# 02-GPRS.net
KiCad netlist of a schematic drawn in Altium Designer
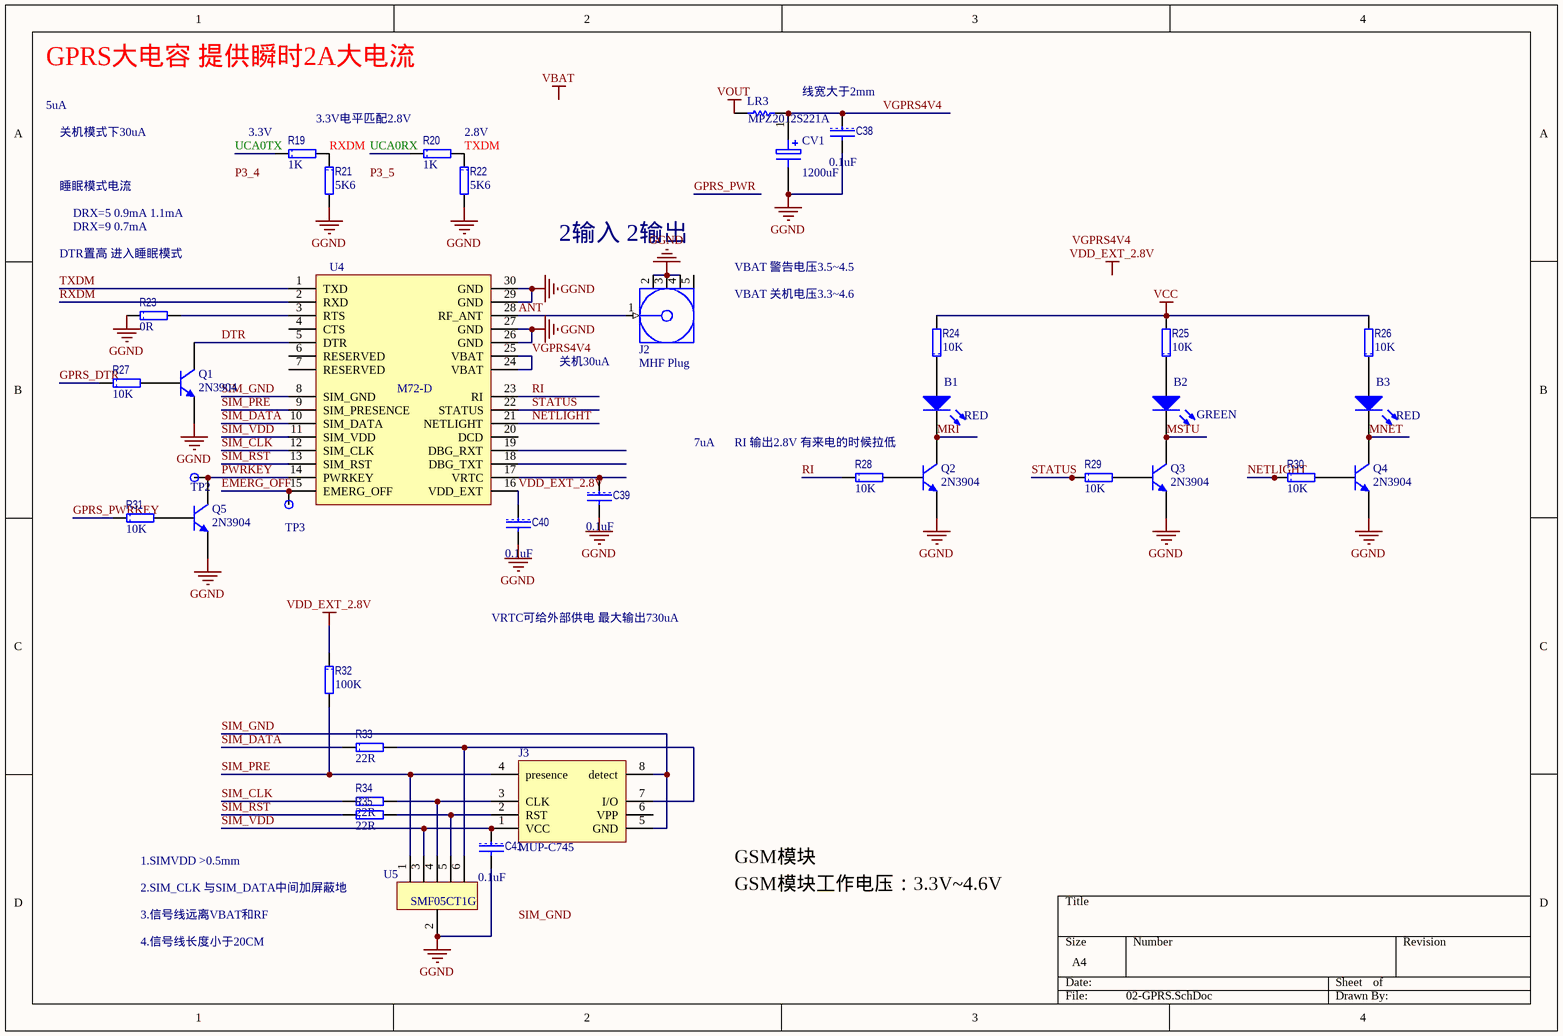
[diagram p0: 02-GPRS.SchDoc]

(export (version "E")
  (design (tool "Eeschema 10.0.6"))
  (components
    (comp (ref "B1")
      (value "RED")
      (footprint "0805LED")
      (description "Typical RED, GREEN, YELLOW, AMBER GaAs LED")
      (fields (field (name "PUBLISHER") "Altium Limited"))
      (libsource (lib "Miscellaneous Devices") (part "LED2"))
    )
    (comp (ref "B2")
      (value "GREEN")
      (footprint "0805LED")
      (description "Typical RED, GREEN, YELLOW, AMBER GaAs LED")
      (fields (field (name "PUBLISHER") "Altium Limited"))
      (libsource (lib "Miscellaneous Devices") (part "LED2"))
    )
    (comp (ref "B3")
      (value "RED")
      (footprint "0805LED")
      (description "Typical RED, GREEN, YELLOW, AMBER GaAs LED")
      (fields (field (name "PUBLISHER") "Altium Limited"))
      (libsource (lib "Miscellaneous Devices") (part "LED2"))
    )
    (comp (ref "C38")
      (value "0.1uF")
      (footprint "1608[0603]C")
      (description "多层陶瓷电容器MLCC - SMD/SMT 0603 0.1uF 50volts X7R 10%")
      (fields (field (name "MANUFACTURER") "TDK") (field (name "MANUFACTURER PART NUMBER") "C1608X7R1H104K"))
      (libsource (lib "*") (part "CAP"))
    )
    (comp (ref "C39")
      (value "0.1uF")
      (footprint "1608[0603]C")
      (description "多层陶瓷电容器MLCC - SMD/SMT 0603 0.1uF 50volts X7R 10%")
      (fields (field (name "MANUFACTURER") "TDK") (field (name "MANUFACTURER PART NUMBER") "C1608X7R1H104K"))
      (libsource (lib "*") (part "CAP"))
    )
    (comp (ref "C40")
      (value "0.1uF")
      (footprint "1608[0603]C")
      (description "多层陶瓷电容器MLCC - SMD/SMT 0603 0.1uF 50volts X7R 10%")
      (fields (field (name "MANUFACTURER") "TDK") (field (name "MANUFACTURER PART NUMBER") "C1608X7R1H104K"))
      (libsource (lib "*") (part "CAP"))
    )
    (comp (ref "C41")
      (value "0.1uF")
      (footprint "1608[0603]C")
      (description "多层陶瓷电容器MLCC - SMD/SMT 0603 0.1uF 50volts X7R 10%")
      (fields (field (name "MANUFACTURER") "TDK") (field (name "MANUFACTURER PART NUMBER") "C1608X7R1H104K"))
      (libsource (lib "*") (part "CAP"))
    )
    (comp (ref "CV1")
      (value "1200uF")
      (footprint "CAPPR5-10x20/H1.1")
      (description "插针 铝质电解电容器 - 带引线 1200uF 10V")
      (fields
        (field (name "MANUFACTURER") "Panasonic Electronic Components")
        (field (name "MANUFACTURER PART NUMBER") "EEU-FC1A122")
      )
      (libsource (lib "*") (part "ELECTRO1"))
    )
    (comp (ref "J2")
      (value "MHF Plug")
      (footprint "MHF[MCB3]-V4")
      (description "插针 RF 连接器 ONBRD IPEX MHF RECEPTACLE")
      (fields
        (field (name "MANUFACTURER") "Taoglas")
        (field (name "MANUFACTURER PART NUMBER") "RECE-20279-001E-01")
      )
      (libsource (lib "Miscellaneous Connectors") (part "COAX-F"))
    )
    (comp (ref "J3")
      (value "MUP-C745")
      (footprint "MUP-C745")
      (description "CON")
      (libsource (lib "*") (part "SIMCARD"))
    )
    (comp (ref "LR3")
      (value "MPZ2012S221A")
      (footprint "2012[0805]")
      (description "电磁干扰滤波珠子、扼流圈和阵列 Ferrite Chip Beads")
      (fields (field (name "MANUFACTURER") "TDK"))
      (libsource (lib "Miscellaneous Devices") (part "Res Semi"))
    )
    (comp (ref "Q1")
      (value "2N3904")
      (footprint "SOT23_N")
      (description "NPN General Purpose Amplifier")
      (fields (field (name "PUBLISHER") "Altium Limited"))
      (libsource (lib "Miscellaneous Devices") (part "2N3904"))
    )
    (comp (ref "Q2")
      (value "2N3904")
      (footprint "SOT23_N")
      (description "NPN General Purpose Amplifier")
      (fields (field (name "PUBLISHER") "Altium Limited"))
      (libsource (lib "Miscellaneous Devices") (part "2N3904"))
    )
    (comp (ref "Q3")
      (value "2N3904")
      (footprint "SOT23_N")
      (description "NPN General Purpose Amplifier")
      (fields (field (name "PUBLISHER") "Altium Limited"))
      (libsource (lib "Miscellaneous Devices") (part "2N3904"))
    )
    (comp (ref "Q4")
      (value "2N3904")
      (footprint "SOT23_N")
      (description "NPN General Purpose Amplifier")
      (fields (field (name "PUBLISHER") "Altium Limited"))
      (libsource (lib "Miscellaneous Devices") (part "2N3904"))
    )
    (comp (ref "Q5")
      (value "2N3904")
      (footprint "SOT23_N")
      (description "NPN General Purpose Amplifier")
      (fields (field (name "PUBLISHER") "Altium Limited"))
      (libsource (lib "Miscellaneous Devices") (part "2N3904"))
    )
    (comp (ref "R19")
      (value "1K")
      (footprint "1608[0603]R")
      (description "厚膜电阻器 - SMD 1/10watt 1.0Kohms 1%")
      (fields
        (field (name "MANUFACTURER") "Vishay / Dale")
        (field (name "MANUFACTURER PART NUMBER") "CRCW06031K00FKEA")
      )
      (libsource (lib "1K 1%") (part "RES"))
    )
    (comp (ref "R20")
      (value "1K")
      (footprint "1608[0603]R")
      (description "厚膜电阻器 - SMD 1/10watt 1.0Kohms 1%")
      (fields
        (field (name "MANUFACTURER") "Vishay / Dale")
        (field (name "MANUFACTURER PART NUMBER") "CRCW06031K00FKEA")
      )
      (libsource (lib "1K 1%") (part "RES"))
    )
    (comp (ref "R21")
      (value "5K6")
      (footprint "1608[0603]R")
      (description "厚膜电阻器 - SMD 1/10watt 10Kohms 1%")
      (fields
        (field (name "MANUFACTURER") "Vishay / Dale")
        (field (name "MANUFACTURER PART NUMBER") "CRCW060310K0FKEA")
      )
      (libsource (lib "10K 1%") (part "RES"))
    )
    (comp (ref "R22")
      (value "5K6")
      (footprint "1608[0603]R")
      (description "厚膜电阻器 - SMD 1/10watt 10Kohms 1%")
      (fields
        (field (name "MANUFACTURER") "Vishay / Dale")
        (field (name "MANUFACTURER PART NUMBER") "CRCW060310K0FKEA")
      )
      (libsource (lib "10K 1%") (part "RES"))
    )
    (comp (ref "R23")
      (value "0R")
      (footprint "1608[0603]R")
      (description "厚膜电阻器 - SMD 1/10watt ZEROohm Jumper")
      (fields
        (field (name "MANUFACTURER") "Vishay / Dale")
        (field (name "MANUFACTURER PART NUMBER") "CRCW06030000ZSTA")
      )
      (libsource (lib "0R 1%") (part "RES"))
    )
    (comp (ref "R24")
      (value "10K")
      (footprint "1608[0603]R")
      (description "厚膜电阻器 - SMD 1/10watt 10Kohms 1%")
      (fields
        (field (name "MANUFACTURER") "Vishay / Dale")
        (field (name "MANUFACTURER PART NUMBER") "CRCW060310K0FKEA")
      )
      (libsource (lib "10K 1%") (part "RES"))
    )
    (comp (ref "R25")
      (value "10K")
      (footprint "1608[0603]R")
      (description "厚膜电阻器 - SMD 1/10watt 10Kohms 1%")
      (fields
        (field (name "MANUFACTURER") "Vishay / Dale")
        (field (name "MANUFACTURER PART NUMBER") "CRCW060310K0FKEA")
      )
      (libsource (lib "10K 1%") (part "RES"))
    )
    (comp (ref "R26")
      (value "10K")
      (footprint "1608[0603]R")
      (description "厚膜电阻器 - SMD 1/10watt 10Kohms 1%")
      (fields
        (field (name "MANUFACTURER") "Vishay / Dale")
        (field (name "MANUFACTURER PART NUMBER") "CRCW060310K0FKEA")
      )
      (libsource (lib "10K 1%") (part "RES"))
    )
    (comp (ref "R27")
      (value "10K")
      (footprint "1608[0603]R")
      (description "厚膜电阻器 - SMD 1/10watt 10Kohms 1%")
      (fields
        (field (name "MANUFACTURER") "Vishay / Dale")
        (field (name "MANUFACTURER PART NUMBER") "CRCW060310K0FKEA")
      )
      (libsource (lib "10K 1%") (part "RES"))
    )
    (comp (ref "R28")
      (value "10K")
      (footprint "1608[0603]R")
      (description "厚膜电阻器 - SMD 1/10watt 10Kohms 1%")
      (fields
        (field (name "MANUFACTURER") "Vishay / Dale")
        (field (name "MANUFACTURER PART NUMBER") "CRCW060310K0FKEA")
      )
      (libsource (lib "10K 1%") (part "RES"))
    )
    (comp (ref "R29")
      (value "10K")
      (footprint "1608[0603]R")
      (description "厚膜电阻器 - SMD 1/10watt 10Kohms 1%")
      (fields
        (field (name "MANUFACTURER") "Vishay / Dale")
        (field (name "MANUFACTURER PART NUMBER") "CRCW060310K0FKEA")
      )
      (libsource (lib "10K 1%") (part "RES"))
    )
    (comp (ref "R30")
      (value "10K")
      (footprint "1608[0603]R")
      (description "厚膜电阻器 - SMD 1/10watt 10Kohms 1%")
      (fields
        (field (name "MANUFACTURER") "Vishay / Dale")
        (field (name "MANUFACTURER PART NUMBER") "CRCW060310K0FKEA")
      )
      (libsource (lib "10K 1%") (part "RES"))
    )
    (comp (ref "R31")
      (value "10K")
      (footprint "1608[0603]R")
      (description "厚膜电阻器 - SMD 1/10watt 10Kohms 1%")
      (fields
        (field (name "MANUFACTURER") "Vishay / Dale")
        (field (name "MANUFACTURER PART NUMBER") "CRCW060310K0FKEA")
      )
      (libsource (lib "10K 1%") (part "RES"))
    )
    (comp (ref "R32")
      (value "100K")
      (footprint "1608[0603]R")
      (description "厚膜电阻器 - SMD 1/10watt 100Kohms 1%")
      (fields
        (field (name "MANUFACTURER") "Vishay / Dale")
        (field (name "MANUFACTURER PART NUMBER") "CRCW0603100KFKEA")
      )
      (libsource (lib "100K 1%") (part "RES"))
    )
    (comp (ref "R33")
      (value "22R")
      (footprint "1608[0603]R")
      (description "厚膜电阻器 - SMD 1/10watt 22ohms 1%")
      (fields
        (field (name "MANUFACTURER") "Vishay / Dale")
        (field (name "MANUFACTURER PART NUMBER") "CRCW060322R0FKEA")
      )
      (libsource (lib "22R 1%") (part "RES"))
    )
    (comp (ref "R34")
      (value "22R")
      (footprint "1608[0603]R")
      (description "厚膜电阻器 - SMD 1/10watt 22ohms 1%")
      (fields
        (field (name "MANUFACTURER") "Vishay / Dale")
        (field (name "MANUFACTURER PART NUMBER") "CRCW060322R0FKEA")
      )
      (libsource (lib "22R 1%") (part "RES"))
    )
    (comp (ref "R35")
      (value "22R")
      (footprint "1608[0603]R")
      (description "厚膜电阻器 - SMD 1/10watt 22ohms 1%")
      (fields
        (field (name "MANUFACTURER") "Vishay / Dale")
        (field (name "MANUFACTURER PART NUMBER") "CRCW060322R0FKEA")
      )
      (libsource (lib "22R 1%") (part "RES"))
    )
    (comp (ref "TP2")
      (value "TP")
      (footprint "TP")
      (description "Test Point")
      (libsource (lib "S3C2440V9") (part "Test Point"))
    )
    (comp (ref "TP3")
      (value "TP")
      (footprint "TP")
      (description "Test Point")
      (libsource (lib "S3C2440V9") (part "Test Point"))
    )
    (comp (ref "U4")
      (value "M72-D")
      (footprint "M72D")
      (description "GSM模块")
      (libsource (lib "*") (part "M72-D"))
    )
    (comp (ref "U5")
      (value "SMF05CT1G")
      (footprint "SOT363-6N")
      (description "TVS二极管阵列 5 Line TVS Array")
      (fields (field (name "MANUFACTURER") "ON Semiconductor"))
      (libsource (lib "*") (part "SMF05CT1G"))
    )
  )
  (nets
    (net (code "1") (name "/ANT") (class "Default")
      (node (ref "J2") (pin "1") (pinfunction "Signal_1") (pintype "input"))
      (node (ref "U4") (pin "28") (pinfunction "RF_ANT_28") (pintype "passive"))
    )
    (net (code "2") (name "/DTR") (class "Default")
      (node (ref "Q1") (pin "3") (pinfunction "C_3") (pintype "passive"))
      (node (ref "U4") (pin "5") (pinfunction "DTR_5") (pintype "passive"))
    )
    (net (code "3") (name "/EMERG_OFF") (class "Default")
      (node (ref "TP3") (pin "1") (pinfunction "TestPoint_1") (pintype "passive"))
      (node (ref "U4") (pin "15") (pinfunction "EMERG_OFF_15") (pintype "passive"))
    )
    (net (code "4") (name "/GPRS_DTR") (class "Default")
      (node (ref "R27") (pin "1") (pinfunction "1_1") (pintype "passive"))
    )
    (net (code "6") (name "/GPRS_PWRKEY") (class "Default")
      (node (ref "R31") (pin "1") (pinfunction "1_1") (pintype "passive"))
    )
    (net (code "7") (name "/MNET") (class "Default")
      (node (ref "B3") (pin "2") (pinfunction "K_2") (pintype "passive"))
      (node (ref "Q4") (pin "3") (pinfunction "C_3") (pintype "passive"))
    )
    (net (code "8") (name "/MRI") (class "Default")
      (node (ref "B1") (pin "2") (pinfunction "K_2") (pintype "passive"))
      (node (ref "Q2") (pin "3") (pinfunction "C_3") (pintype "passive"))
    )
    (net (code "9") (name "/MSTU") (class "Default")
      (node (ref "B2") (pin "2") (pinfunction "K_2") (pintype "passive"))
      (node (ref "Q3") (pin "3") (pinfunction "C_3") (pintype "passive"))
    )
    (net (code "10") (name "/NETLIGHT") (class "Default")
      (node (ref "R30") (pin "1") (pinfunction "1_1") (pintype "passive"))
      (node (ref "U4") (pin "21") (pinfunction "NETLIGHT_21") (pintype "passive"))
    )
    (net (code "13") (name "/PWRKEY") (class "Default")
      (node (ref "Q5") (pin "3") (pinfunction "C_3") (pintype "passive"))
      (node (ref "TP2") (pin "1") (pinfunction "TestPoint_1") (pintype "passive"))
      (node (ref "U4") (pin "14") (pinfunction "PWRKEY_14") (pintype "passive"))
    )
    (net (code "14") (name "/RI") (class "Default")
      (node (ref "R28") (pin "1") (pinfunction "1_1") (pintype "passive"))
      (node (ref "U4") (pin "23") (pinfunction "RI_23") (pintype "passive"))
    )
    (net (code "15") (name "/RXDM") (class "Default")
      (node (ref "R19") (pin "2") (pinfunction "2_2") (pintype "passive"))
      (node (ref "R21") (pin "1") (pinfunction "1_1") (pintype "passive"))
      (node (ref "U4") (pin "2") (pinfunction "RXD_2") (pintype "passive"))
    )
    (net (code "16") (name "/SIM_CLK") (class "Default")
      (node (ref "R34") (pin "1") (pinfunction "1_1") (pintype "passive"))
      (node (ref "U4") (pin "12") (pinfunction "SIM_CLK_12") (pintype "passive"))
    )
    (net (code "17") (name "/SIM_DATA") (class "Default")
      (node (ref "R33") (pin "1") (pinfunction "1_1") (pintype "passive"))
      (node (ref "U4") (pin "10") (pinfunction "SIM_DATA_10") (pintype "passive"))
    )
    (net (code "18") (name "/SIM_GND") (class "Default")
      (node (ref "J3") (pin "5") (pinfunction "GND_5") (pintype "passive"))
      (node (ref "J3") (pin "8") (pinfunction "detect_8") (pintype "passive"))
      (node (ref "U4") (pin "8") (pinfunction "SIM_GND_8") (pintype "passive"))
    )
    (net (code "19") (name "/SIM_PRE") (class "Default")
      (node (ref "J3") (pin "4") (pinfunction "presence_4") (pintype "passive"))
      (node (ref "R32") (pin "2") (pinfunction "2_2") (pintype "passive"))
      (node (ref "U4") (pin "9") (pinfunction "SIM_PRESENCE_9") (pintype "passive"))
      (node (ref "U5") (pin "1") (pinfunction "1_1") (pintype "passive"))
    )
    (net (code "20") (name "/SIM_RST") (class "Default")
      (node (ref "R35") (pin "1") (pinfunction "1_1") (pintype "passive"))
      (node (ref "U4") (pin "13") (pinfunction "SIM_RST_13") (pintype "passive"))
    )
    (net (code "21") (name "/SIM_VDD") (class "Default")
      (node (ref "C41") (pin "1") (pinfunction "1_1") (pintype "passive"))
      (node (ref "J3") (pin "1") (pinfunction "VCC_1") (pintype "passive"))
      (node (ref "U4") (pin "11") (pinfunction "SIM_VDD_11") (pintype "passive"))
      (node (ref "U5") (pin "3") (pinfunction "3_3") (pintype "passive"))
    )
    (net (code "22") (name "/STATUS") (class "Default")
      (node (ref "R29") (pin "1") (pinfunction "1_1") (pintype "passive"))
      (node (ref "U4") (pin "22") (pinfunction "STATUS_22") (pintype "passive"))
    )
    (net (code "23") (name "/TXDM") (class "Default")
      (node (ref "R20") (pin "2") (pinfunction "2_2") (pintype "passive"))
      (node (ref "R22") (pin "1") (pinfunction "1_1") (pintype "passive"))
      (node (ref "U4") (pin "1") (pinfunction "TXD_1") (pintype "passive"))
    )
    (net (code "24") (name "/UCA0RX") (class "Default")
      (node (ref "R20") (pin "1") (pinfunction "1_1") (pintype "passive"))
    )
    (net (code "25") (name "/UCA0TX") (class "Default")
      (node (ref "R19") (pin "1") (pinfunction "1_1") (pintype "passive"))
    )
    (net (code "26") (name "/VGPRS4V4") (class "Default")
      (node (ref "C38") (pin "1") (pinfunction "1_1") (pintype "passive"))
      (node (ref "CV1") (pin "1") (pinfunction "1_1") (pintype "passive"))
      (node (ref "LR3") (pin "2") (pinfunction "2_2") (pintype "passive"))
      (node (ref "U4") (pin "24") (pinfunction "VBAT_24") (pintype "passive"))
      (node (ref "U4") (pin "25") (pinfunction "VBAT_25") (pintype "passive"))
    )
    (net (code "27") (name "GGND") (class "Default")
      (node (ref "C38") (pin "2") (pinfunction "2_2") (pintype "passive"))
      (node (ref "C39") (pin "2") (pinfunction "2_2") (pintype "passive"))
      (node (ref "C40") (pin "2") (pinfunction "2_2") (pintype "passive"))
      (node (ref "C41") (pin "2") (pinfunction "2_2") (pintype "passive"))
      (node (ref "CV1") (pin "2") (pinfunction "2_2") (pintype "passive"))
      (node (ref "J2") (pin "2") (pinfunction "GND_2") (pintype "power_in"))
      (node (ref "J2") (pin "3") (pinfunction "GND_3") (pintype "power_in"))
      (node (ref "J2") (pin "4") (pinfunction "GND_4") (pintype "power_in"))
      (node (ref "Q1") (pin "1") (pinfunction "E_1") (pintype "passive"))
      (node (ref "Q2") (pin "1") (pinfunction "E_1") (pintype "passive"))
      (node (ref "Q3") (pin "1") (pinfunction "E_1") (pintype "passive"))
      (node (ref "Q4") (pin "1") (pinfunction "E_1") (pintype "passive"))
      (node (ref "Q5") (pin "1") (pinfunction "E_1") (pintype "passive"))
      (node (ref "R21") (pin "2") (pinfunction "2_2") (pintype "passive"))
      (node (ref "R22") (pin "2") (pinfunction "2_2") (pintype "passive"))
      (node (ref "R23") (pin "1") (pinfunction "1_1") (pintype "passive"))
      (node (ref "U4") (pin "26") (pinfunction "GND_26") (pintype "passive"))
      (node (ref "U4") (pin "27") (pinfunction "GND_27") (pintype "passive"))
      (node (ref "U4") (pin "29") (pinfunction "GND_29") (pintype "passive"))
      (node (ref "U4") (pin "30") (pinfunction "GND_30") (pintype "passive"))
      (node (ref "U5") (pin "2") (pinfunction "2_2") (pintype "passive"))
    )
    (net (code "28") (name "Net-(B1-A)") (class "Default")
      (node (ref "B1") (pin "1") (pinfunction "A_1") (pintype "passive"))
      (node (ref "R24") (pin "1") (pinfunction "1_1") (pintype "passive"))
    )
    (net (code "29") (name "Net-(B2-A)") (class "Default")
      (node (ref "B2") (pin "1") (pinfunction "A_1") (pintype "passive"))
      (node (ref "R25") (pin "1") (pinfunction "1_1") (pintype "passive"))
    )
    (net (code "30") (name "Net-(B3-A)") (class "Default")
      (node (ref "B3") (pin "1") (pinfunction "A_1") (pintype "passive"))
      (node (ref "R26") (pin "1") (pinfunction "1_1") (pintype "passive"))
    )
    (net (code "31") (name "Net-(J3-CLK)") (class "Default")
      (node (ref "J3") (pin "3") (pinfunction "CLK_3") (pintype "passive"))
      (node (ref "R34") (pin "2") (pinfunction "2_2") (pintype "passive"))
      (node (ref "U5") (pin "4") (pinfunction "4_4") (pintype "passive"))
    )
    (net (code "32") (name "Net-(J3-I{slash}O)") (class "Default")
      (node (ref "J3") (pin "7") (pinfunction "I/O_7") (pintype "passive"))
      (node (ref "R33") (pin "2") (pinfunction "2_2") (pintype "passive"))
      (node (ref "U5") (pin "6") (pinfunction "6_6") (pintype "passive"))
    )
    (net (code "33") (name "Net-(J3-RST)") (class "Default")
      (node (ref "J3") (pin "2") (pinfunction "RST_2") (pintype "passive"))
      (node (ref "R35") (pin "2") (pinfunction "2_2") (pintype "passive"))
      (node (ref "U5") (pin "5") (pinfunction "5_5") (pintype "passive"))
    )
    (net (code "34") (name "Net-(Q1-B)") (class "Default")
      (node (ref "Q1") (pin "2") (pinfunction "B_2") (pintype "passive"))
      (node (ref "R27") (pin "2") (pinfunction "2_2") (pintype "passive"))
    )
    (net (code "35") (name "Net-(Q2-B)") (class "Default")
      (node (ref "Q2") (pin "2") (pinfunction "B_2") (pintype "passive"))
      (node (ref "R28") (pin "2") (pinfunction "2_2") (pintype "passive"))
    )
    (net (code "36") (name "Net-(Q3-B)") (class "Default")
      (node (ref "Q3") (pin "2") (pinfunction "B_2") (pintype "passive"))
      (node (ref "R29") (pin "2") (pinfunction "2_2") (pintype "passive"))
    )
    (net (code "37") (name "Net-(Q4-B)") (class "Default")
      (node (ref "Q4") (pin "2") (pinfunction "B_2") (pintype "passive"))
      (node (ref "R30") (pin "2") (pinfunction "2_2") (pintype "passive"))
    )
    (net (code "38") (name "Net-(Q5-B)") (class "Default")
      (node (ref "Q5") (pin "2") (pinfunction "B_2") (pintype "passive"))
      (node (ref "R31") (pin "2") (pinfunction "2_2") (pintype "passive"))
    )
    (net (code "39") (name "Net-(U4-RTS)") (class "Default")
      (node (ref "R23") (pin "2") (pinfunction "2_2") (pintype "passive"))
      (node (ref "U4") (pin "3") (pinfunction "RTS_3") (pintype "passive"))
    )
    (net (code "40") (name "Net-(U4-VRTC)") (class "Default")
      (node (ref "C39") (pin "1") (pinfunction "1_1") (pintype "passive"))
      (node (ref "U4") (pin "17") (pinfunction "VRTC_17") (pintype "passive"))
    )
    (net (code "42") (name "VCC") (class "Default")
      (node (ref "R24") (pin "2") (pinfunction "2_2") (pintype "passive"))
      (node (ref "R25") (pin "2") (pinfunction "2_2") (pintype "passive"))
      (node (ref "R26") (pin "2") (pinfunction "2_2") (pintype "passive"))
    )
    (net (code "43") (name "VDD_EXT_2.8V") (class "Default")
      (node (ref "C40") (pin "1") (pinfunction "1_1") (pintype "passive"))
      (node (ref "R32") (pin "1") (pinfunction "1_1") (pintype "passive"))
      (node (ref "U4") (pin "16") (pinfunction "VDD_EXT_16") (pintype "passive"))
    )
    (net (code "44") (name "VOUT") (class "Default")
      (node (ref "LR3") (pin "1") (pinfunction "1_1") (pintype "passive"))
    )
    (net (code "45") (name "unconnected-(J2-GND-Pad5)") (class "Default")
      (node (ref "J2") (pin "5") (pinfunction "GND_5") (pintype "power_in"))
    )
    (net (code "46") (name "unconnected-(J3-VPP-Pad6)") (class "Default")
      (node (ref "J3") (pin "6") (pinfunction "VPP_6") (pintype "passive"))
    )
    (net (code "47") (name "unconnected-(U4-CTS-Pad4)") (class "Default")
      (node (ref "U4") (pin "4") (pinfunction "CTS_4") (pintype "passive"))
    )
    (net (code "48") (name "unconnected-(U4-DBG_RXT-Pad19)") (class "Default")
      (node (ref "U4") (pin "19") (pinfunction "DBG_RXT_19") (pintype "passive"))
    )
    (net (code "49") (name "unconnected-(U4-DBG_TXT-Pad18)") (class "Default")
      (node (ref "U4") (pin "18") (pinfunction "DBG_TXT_18") (pintype "passive"))
    )
    (net (code "50") (name "unconnected-(U4-DCD-Pad20)") (class "Default")
      (node (ref "U4") (pin "20") (pinfunction "DCD_20") (pintype "passive"))
    )
    (net (code "51") (name "unconnected-(U4-RESERVED-Pad6)") (class "Default")
      (node (ref "U4") (pin "6") (pinfunction "RESERVED_6") (pintype "passive"))
    )
    (net (code "52") (name "unconnected-(U4-RESERVED-Pad7)") (class "Default")
      (node (ref "U4") (pin "7") (pinfunction "RESERVED_7") (pintype "passive"))
    )
  )
)
